# PRIMERAPRUEBA.net
KiCad netlist of a schematic drawn in EAGLE
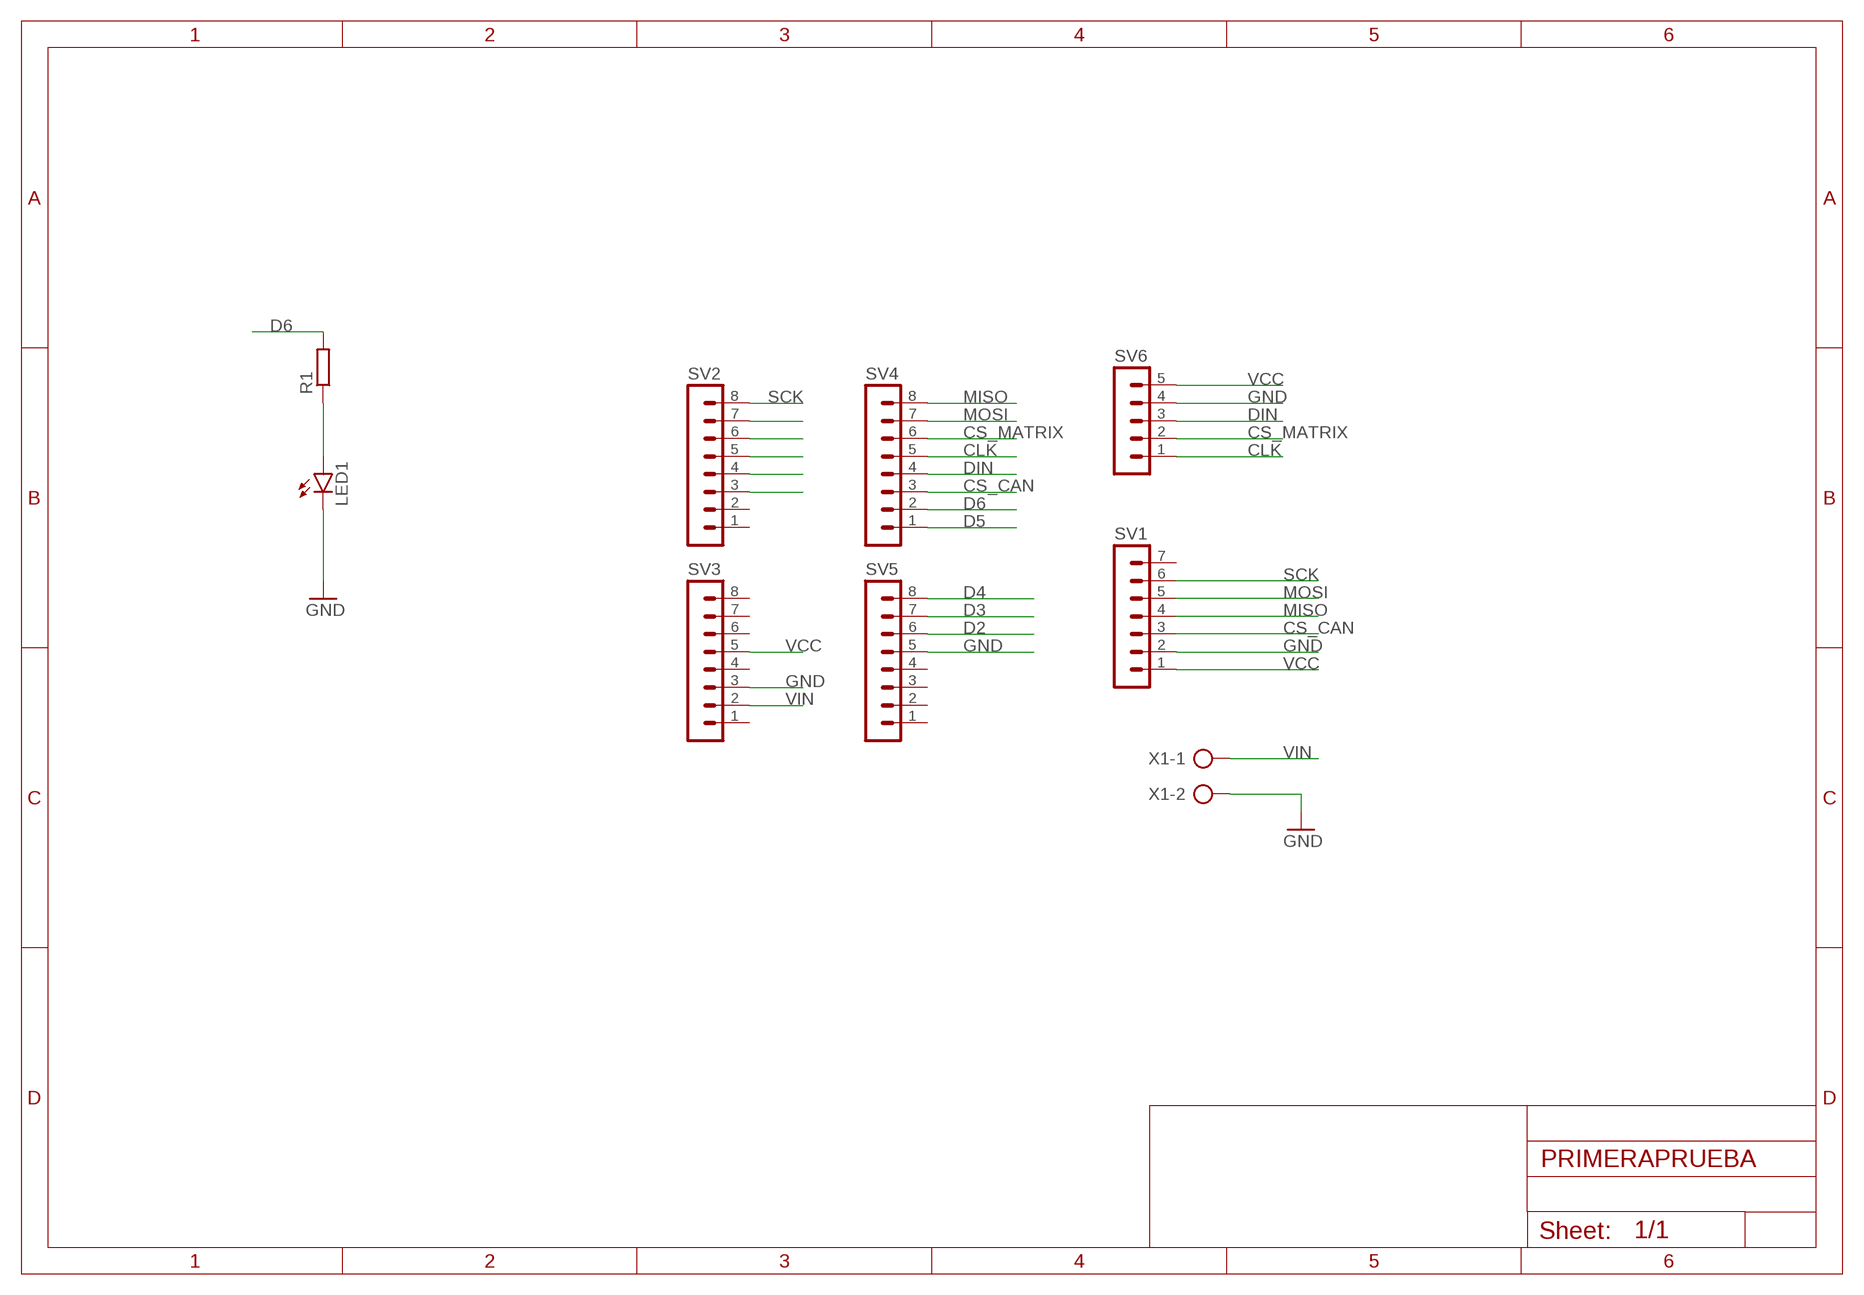
[diagram p0: schematic, sheet 1]

(export (version "E")
  (design (tool "Eeschema 10.0.6"))
  (components
    (comp (ref "LED1")
      (value "LED5MM")
      (footprint "eagle-import:LED5MM")
      (libsource (lib "eagle-import") (part "LED5MM"))
    )
    (comp (ref "R1")
      (value "R-EU_0204/7")
      (footprint "eagle-import:0204_7")
      (libsource (lib "eagle-import") (part "R-EU_0204/7"))
    )
    (comp (ref "SV1")
      (value "MA07-1")
      (footprint "eagle-import:MA07-1")
      (libsource (lib "eagle-import") (part "MA07-1"))
    )
    (comp (ref "SV2")
      (value "MA08-1")
      (footprint "eagle-import:MA08-1")
      (libsource (lib "eagle-import") (part "MA08-1"))
    )
    (comp (ref "SV3")
      (value "MA08-1")
      (footprint "eagle-import:MA08-1")
      (libsource (lib "eagle-import") (part "MA08-1"))
    )
    (comp (ref "SV4")
      (value "MA08-1")
      (footprint "eagle-import:MA08-1")
      (libsource (lib "eagle-import") (part "MA08-1"))
    )
    (comp (ref "SV5")
      (value "MA08-1")
      (footprint "eagle-import:MA08-1")
      (libsource (lib "eagle-import") (part "MA08-1"))
    )
    (comp (ref "SV6")
      (value "MA05-1")
      (footprint "eagle-import:MA05-1")
      (libsource (lib "eagle-import") (part "MA05-1"))
    )
    (comp (ref "X1")
      (value "AK300/2")
      (footprint "eagle-import:AK300_2")
      (libsource (lib "eagle-import") (part "AK300/2"))
    )
  )
  (nets
    (net (code "1") (name "/CLK") (class "Default")
      (node (ref "SV4") (pin "5") (pinfunction "5_5") (pintype "passive"))
      (node (ref "SV6") (pin "1") (pinfunction "1_1") (pintype "passive"))
    )
    (net (code "2") (name "/CS_CAN") (class "Default")
      (node (ref "SV1") (pin "3") (pinfunction "3_3") (pintype "passive"))
      (node (ref "SV4") (pin "3") (pinfunction "3_3") (pintype "passive"))
    )
    (net (code "3") (name "/CS_MATRIX") (class "Default")
      (node (ref "SV4") (pin "6") (pinfunction "6_6") (pintype "passive"))
      (node (ref "SV6") (pin "2") (pinfunction "2_2") (pintype "passive"))
    )
    (net (code "4") (name "/D2") (class "Default")
      (node (ref "SV5") (pin "6") (pinfunction "6_6") (pintype "passive"))
    )
    (net (code "5") (name "/D3") (class "Default")
      (node (ref "SV5") (pin "7") (pinfunction "7_7") (pintype "passive"))
    )
    (net (code "6") (name "/D4") (class "Default")
      (node (ref "SV5") (pin "8") (pinfunction "8_8") (pintype "passive"))
    )
    (net (code "7") (name "/D5") (class "Default")
      (node (ref "SV4") (pin "1") (pinfunction "1_1") (pintype "passive"))
    )
    (net (code "8") (name "/D6") (class "Default")
      (node (ref "R1") (pin "2") (pinfunction "2_2") (pintype "passive"))
      (node (ref "SV4") (pin "2") (pinfunction "2_2") (pintype "passive"))
    )
    (net (code "9") (name "/DIN") (class "Default")
      (node (ref "SV4") (pin "4") (pinfunction "4_4") (pintype "passive"))
      (node (ref "SV6") (pin "3") (pinfunction "3_3") (pintype "passive"))
    )
    (net (code "10") (name "/MISO") (class "Default")
      (node (ref "SV1") (pin "4") (pinfunction "4_4") (pintype "passive"))
      (node (ref "SV4") (pin "8") (pinfunction "8_8") (pintype "passive"))
    )
    (net (code "11") (name "/MOSI") (class "Default")
      (node (ref "SV1") (pin "5") (pinfunction "5_5") (pintype "passive"))
      (node (ref "SV4") (pin "7") (pinfunction "7_7") (pintype "passive"))
    )
    (net (code "12") (name "/SCK") (class "Default")
      (node (ref "SV1") (pin "6") (pinfunction "6_6") (pintype "passive"))
      (node (ref "SV2") (pin "8") (pinfunction "8_8") (pintype "passive"))
    )
    (net (code "13") (name "/VCC") (class "Default")
      (node (ref "SV1") (pin "1") (pinfunction "1_1") (pintype "passive"))
      (node (ref "SV3") (pin "5") (pinfunction "5_5") (pintype "passive"))
      (node (ref "SV6") (pin "5") (pinfunction "5_5") (pintype "passive"))
    )
    (net (code "14") (name "/VIN") (class "Default")
      (node (ref "SV3") (pin "2") (pinfunction "2_2") (pintype "passive"))
      (node (ref "X1") (pin "1") (pinfunction "KL_1") (pintype "passive"))
    )
    (net (code "15") (name "GND") (class "Default")
      (node (ref "LED1") (pin "K") (pinfunction "C_K") (pintype "passive"))
      (node (ref "SV1") (pin "2") (pinfunction "2_2") (pintype "passive"))
      (node (ref "SV3") (pin "3") (pinfunction "3_3") (pintype "passive"))
      (node (ref "SV5") (pin "5") (pinfunction "5_5") (pintype "passive"))
      (node (ref "SV6") (pin "4") (pinfunction "4_4") (pintype "passive"))
      (node (ref "X1") (pin "2") (pinfunction "KL_2") (pintype "passive"))
    )
    (net (code "16") (name "Net-(LED1-PadA)") (class "Default")
      (node (ref "LED1") (pin "A") (pinfunction "A_A") (pintype "passive"))
      (node (ref "R1") (pin "1") (pinfunction "1_1") (pintype "passive"))
    )
    (net (code "17") (name "unconnected-(SV1-Pad7)") (class "Default")
      (node (ref "SV1") (pin "7") (pinfunction "7_7") (pintype "passive"))
    )
    (net (code "18") (name "unconnected-(SV2-Pad1)") (class "Default")
      (node (ref "SV2") (pin "1") (pinfunction "1_1") (pintype "passive"))
    )
    (net (code "19") (name "unconnected-(SV2-Pad2)") (class "Default")
      (node (ref "SV2") (pin "2") (pinfunction "2_2") (pintype "passive"))
    )
    (net (code "20") (name "unconnected-(SV2-Pad3)") (class "Default")
      (node (ref "SV2") (pin "3") (pinfunction "3_3") (pintype "passive"))
    )
    (net (code "21") (name "unconnected-(SV2-Pad4)") (class "Default")
      (node (ref "SV2") (pin "4") (pinfunction "4_4") (pintype "passive"))
    )
    (net (code "22") (name "unconnected-(SV2-Pad5)") (class "Default")
      (node (ref "SV2") (pin "5") (pinfunction "5_5") (pintype "passive"))
    )
    (net (code "23") (name "unconnected-(SV2-Pad6)") (class "Default")
      (node (ref "SV2") (pin "6") (pinfunction "6_6") (pintype "passive"))
    )
    (net (code "24") (name "unconnected-(SV2-Pad7)") (class "Default")
      (node (ref "SV2") (pin "7") (pinfunction "7_7") (pintype "passive"))
    )
    (net (code "25") (name "unconnected-(SV3-Pad1)") (class "Default")
      (node (ref "SV3") (pin "1") (pinfunction "1_1") (pintype "passive"))
    )
    (net (code "26") (name "unconnected-(SV3-Pad4)") (class "Default")
      (node (ref "SV3") (pin "4") (pinfunction "4_4") (pintype "passive"))
    )
    (net (code "27") (name "unconnected-(SV3-Pad6)") (class "Default")
      (node (ref "SV3") (pin "6") (pinfunction "6_6") (pintype "passive"))
    )
    (net (code "28") (name "unconnected-(SV3-Pad7)") (class "Default")
      (node (ref "SV3") (pin "7") (pinfunction "7_7") (pintype "passive"))
    )
    (net (code "29") (name "unconnected-(SV3-Pad8)") (class "Default")
      (node (ref "SV3") (pin "8") (pinfunction "8_8") (pintype "passive"))
    )
    (net (code "30") (name "unconnected-(SV5-Pad1)") (class "Default")
      (node (ref "SV5") (pin "1") (pinfunction "1_1") (pintype "passive"))
    )
    (net (code "31") (name "unconnected-(SV5-Pad2)") (class "Default")
      (node (ref "SV5") (pin "2") (pinfunction "2_2") (pintype "passive"))
    )
    (net (code "32") (name "unconnected-(SV5-Pad3)") (class "Default")
      (node (ref "SV5") (pin "3") (pinfunction "3_3") (pintype "passive"))
    )
    (net (code "33") (name "unconnected-(SV5-Pad4)") (class "Default")
      (node (ref "SV5") (pin "4") (pinfunction "4_4") (pintype "passive"))
    )
  )
)
